# ExternalLEDsXSMALL.net
KiCad netlist of a schematic drawn in EAGLE
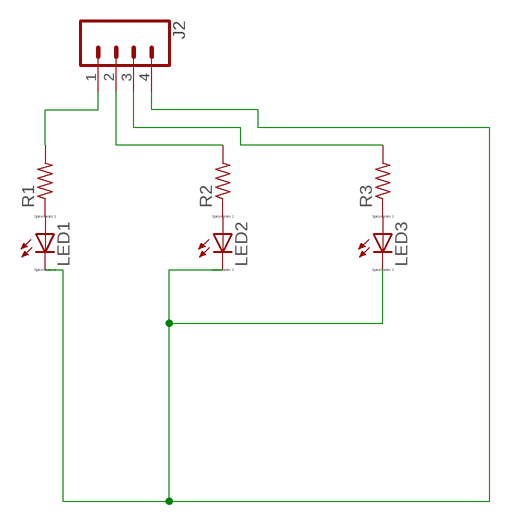
[diagram p0: schematic, sheet 1]

(export (version "E")
  (design (tool "Eeschema 10.0.6"))
  (components
    (comp (ref "J2")
      (value "CONN_04POLAR")
      (footprint "eagle-import:MOLEX-1X4")
      (libsource (lib "eagle-import") (part "CONN_04POLAR"))
    )
    (comp (ref "LED1")
      (value "LED_E")
      (footprint "eagle-import:LED_1206")
      (libsource (lib "eagle-import") (part "LED_E"))
    )
    (comp (ref "LED2")
      (value "LED_E")
      (footprint "eagle-import:LED_1206")
      (libsource (lib "eagle-import") (part "LED_E"))
    )
    (comp (ref "LED3")
      (value "LED_E")
      (footprint "eagle-import:LED_1206")
      (libsource (lib "eagle-import") (part "LED_E"))
    )
    (comp (ref "R1")
      (value "R-US_0204/7")
      (footprint "eagle-import:0204_7")
      (libsource (lib "eagle-import") (part "R-US_0204/7"))
    )
    (comp (ref "R2")
      (value "R-US_0204/7")
      (footprint "eagle-import:0204_7")
      (libsource (lib "eagle-import") (part "R-US_0204/7"))
    )
    (comp (ref "R3")
      (value "R-US_0204/7")
      (footprint "eagle-import:0204_7")
      (libsource (lib "eagle-import") (part "R-US_0204/7"))
    )
  )
  (nets
    (net (code "1") (name "Net-(J2-Pad1)") (class "Default")
      (node (ref "J2") (pin "1") (pinfunction "1_1") (pintype "passive"))
      (node (ref "R1") (pin "2") (pinfunction "2_2") (pintype "passive"))
    )
    (net (code "2") (name "Net-(J2-Pad2)") (class "Default")
      (node (ref "J2") (pin "2") (pinfunction "2_2") (pintype "passive"))
      (node (ref "R2") (pin "2") (pinfunction "2_2") (pintype "passive"))
    )
    (net (code "3") (name "Net-(J2-Pad3)") (class "Default")
      (node (ref "J2") (pin "3") (pinfunction "3_3") (pintype "passive"))
      (node (ref "R3") (pin "2") (pinfunction "2_2") (pintype "passive"))
    )
    (net (code "4") (name "Net-(J2-Pad4)") (class "Default")
      (node (ref "J2") (pin "4") (pinfunction "4_4") (pintype "passive"))
      (node (ref "LED1") (pin "C") (pinfunction "C_C") (pintype "passive"))
      (node (ref "LED2") (pin "C") (pinfunction "C_C") (pintype "passive"))
      (node (ref "LED3") (pin "C") (pinfunction "C_C") (pintype "passive"))
    )
    (net (code "5") (name "Net-(LED1-PadA)") (class "Default")
      (node (ref "LED1") (pin "A") (pinfunction "A_A") (pintype "passive"))
      (node (ref "R1") (pin "1") (pinfunction "1_1") (pintype "passive"))
    )
    (net (code "6") (name "Net-(LED2-PadA)") (class "Default")
      (node (ref "LED2") (pin "A") (pinfunction "A_A") (pintype "passive"))
      (node (ref "R2") (pin "1") (pinfunction "1_1") (pintype "passive"))
    )
    (net (code "7") (name "Net-(LED3-PadA)") (class "Default")
      (node (ref "LED3") (pin "A") (pinfunction "A_A") (pintype "passive"))
      (node (ref "R3") (pin "1") (pinfunction "1_1") (pintype "passive"))
    )
  )
)
